# PowerTree.net
KiCad netlist of a schematic drawn in Altium Designer
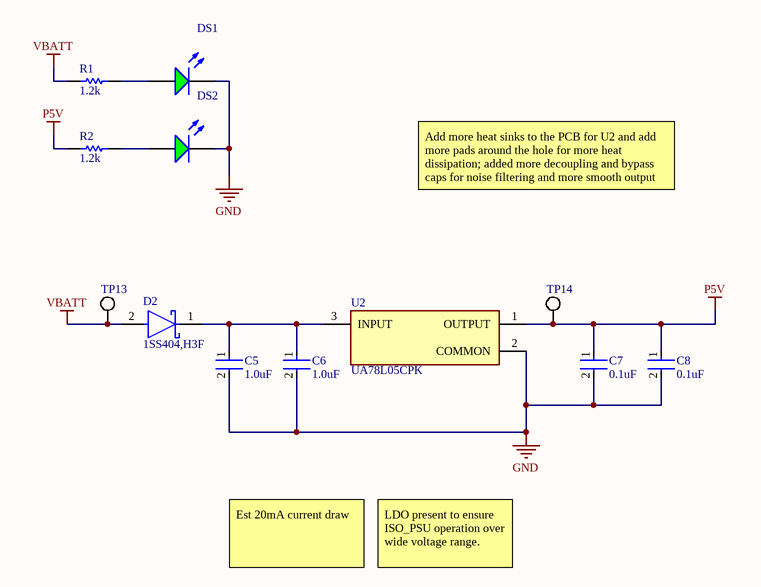
[diagram p0: PowerTree.SchDoc]

(export (version "E")
  (design (tool "Eeschema 10.0.6"))
  (components
    (comp (ref "C5")
      (value "1.0uF")
      (footprint "FP-1206-L_3_2_0_2-W_1_6_0-IPC_A")
      (description "General Purpose Ceramic Capacitor, 1206, 1uF, 10%, X7R, 15%, 50V")
      (fields (field (name "TOLERANCE") "10%") (field (name "VOLTAGE") "25V"))
      (libsource (lib "Altium Content Vault") (part "b4654b650e69147ec39a6b967a45e02"))
    )
    (comp (ref "C6")
      (value "1.0uF")
      (footprint "FP-1206-L_3_2_0_2-W_1_6_0-IPC_A")
      (description "General Purpose Ceramic Capacitor, 1206, 1uF, 10%, X7R, 15%, 50V")
      (fields (field (name "TOLERANCE") "10%") (field (name "VOLTAGE") "25V"))
      (libsource (lib "Altium Content Vault") (part "b4654b650e69147ec39a6b967a45e02"))
    )
    (comp (ref "C7")
      (value "0.1uF")
      (footprint "FP-1206-L_3_2_0_2-W_1_6_0-IPC_C")
      (description "General Purpose Ceramic Capacitor, 1206, 100nF, 5%, X7R, 15%, 100V")
      (fields (field (name "TOLERANCE") "5%") (field (name "VOLTAGE") "100V"))
      (libsource (lib "Altium Content Vault") (part "b4654b650e69147ec39a6b967a45e02"))
    )
    (comp (ref "C8")
      (value "0.1uF")
      (footprint "FP-1206-L_3_2_0_2-W_1_6_0-IPC_C")
      (description "General Purpose Ceramic Capacitor, 1206, 100nF, 5%, X7R, 15%, 100V")
      (fields (field (name "TOLERANCE") "5%") (field (name "VOLTAGE") "100V"))
      (libsource (lib "Altium Content Vault") (part "b4654b650e69147ec39a6b967a45e02"))
    )
    (comp (ref "D2")
      (value "1SS404,H3F")
      (footprint "FP-SOD-323-MFG")
      (description "DIODE SCHOTTKY 20V 300MA USC")
      (libsource (lib "Altium Content Vault") (part "1d6ec82d83fb6aee721767c19dac4b9"))
    )
    (comp (ref "DS1")
      (value "597-3311-407F")
      (footprint "DIAL-597-3311-407F_V")
      (description "Single Color LED, Green, Water Clear, 2mm")
      (libsource (lib "University of California Riverside - FSAE") (part "LED-GREEN-AK-2"))
    )
    (comp (ref "DS2")
      (value "597-3311-407F")
      (footprint "DIAL-597-3311-407F_V")
      (description "Single Color LED, Green, Water Clear, 2mm")
      (libsource (lib "University of California Riverside - FSAE") (part "LED-GREEN-AK-2"))
    )
    (comp (ref "R1")
      (value "1.2k")
      (footprint "RESC3216X70X50LL05T20")
      (fields (field (name "PART NUMBER") "ERJ8ENF1201V") (field (name "MANUFACTURER") "Panasonic"))
      (libsource (lib "Altium Content Vault") (part "RES"))
    )
    (comp (ref "R2")
      (value "1.2k")
      (footprint "RESC3216X70X50LL05T20")
      (fields (field (name "PART NUMBER") "ERJ8ENF1201V") (field (name "MANUFACTURER") "Panasonic"))
      (libsource (lib "Altium Content Vault") (part "RES"))
    )
    (comp (ref "TP13")
      (value "~")
      (footprint "FOOTPRINT-GENERIC-TP-VIA-1MM")
      (libsource (lib "University of California Riverside - FSAE") (part "Misc-Generic-TP"))
    )
    (comp (ref "TP14")
      (value "~")
      (footprint "FOOTPRINT-GENERIC-TP-VIA-1MM")
      (libsource (lib "University of California Riverside - FSAE") (part "Misc-Generic-TP"))
    )
    (comp (ref "U2")
      (value "UA78L05CPK")
      (footprint "FP-PK0003A-MFG")
      (description "IC REG LINEAR 5V 100MA SOT89-3")
      (fields
        (field (name "MANUFACTURER") "Texas Instruments")
        (field (name "OCTOPART") "https://octopart.com/ua78l05cpk-texas+instruments-525289")
      )
      (libsource (lib "Altium Content Vault") (part "2049580646e915a67e9ed9ae0049ef9"))
    )
  )
  (nets
    (net (code "1") (name "GND") (class "Default")
      (node (ref "C5") (pin "2") (pinfunction "2_2") (pintype "passive"))
      (node (ref "C6") (pin "2") (pinfunction "2_2") (pintype "passive"))
      (node (ref "C7") (pin "2") (pinfunction "2_2") (pintype "passive"))
      (node (ref "C8") (pin "2") (pinfunction "2_2") (pintype "passive"))
      (node (ref "DS1") (pin "2") (pinfunction "K_2") (pintype "passive"))
      (node (ref "DS2") (pin "2") (pinfunction "K_2") (pintype "passive"))
      (node (ref "U2") (pin "2") (pinfunction "COMMON_2") (pintype "power_in"))
    )
    (net (code "2") (name "Net-(D2-C)") (class "Default")
      (node (ref "C5") (pin "1") (pinfunction "1_1") (pintype "passive"))
      (node (ref "C6") (pin "1") (pinfunction "1_1") (pintype "passive"))
      (node (ref "D2") (pin "1") (pinfunction "C_1") (pintype "passive"))
      (node (ref "U2") (pin "3") (pinfunction "INPUT_3") (pintype "power_in"))
    )
    (net (code "3") (name "Net-(DS1-A)") (class "Default")
      (node (ref "DS1") (pin "1") (pinfunction "A_1") (pintype "passive"))
      (node (ref "R1") (pin "2") (pinfunction "2_2") (pintype "passive"))
    )
    (net (code "4") (name "Net-(DS2-A)") (class "Default")
      (node (ref "DS2") (pin "1") (pinfunction "A_1") (pintype "passive"))
      (node (ref "R2") (pin "2") (pinfunction "2_2") (pintype "passive"))
    )
    (net (code "5") (name "P5V") (class "Default")
      (node (ref "C7") (pin "1") (pinfunction "1_1") (pintype "passive"))
      (node (ref "C8") (pin "1") (pinfunction "1_1") (pintype "passive"))
      (node (ref "R2") (pin "1") (pinfunction "1_1") (pintype "passive"))
      (node (ref "TP14") (pin "1") (pinfunction "TP_1") (pintype "passive"))
      (node (ref "U2") (pin "1") (pinfunction "OUTPUT_1") (pintype "power_in"))
    )
    (net (code "6") (name "VBATT") (class "Default")
      (node (ref "D2") (pin "2") (pinfunction "A_2") (pintype "passive"))
      (node (ref "R1") (pin "1") (pinfunction "1_1") (pintype "passive"))
      (node (ref "TP13") (pin "1") (pinfunction "TP_1") (pintype "passive"))
    )
  )
)
